# GPS.net
KiCad netlist of a schematic drawn in Altium Designer
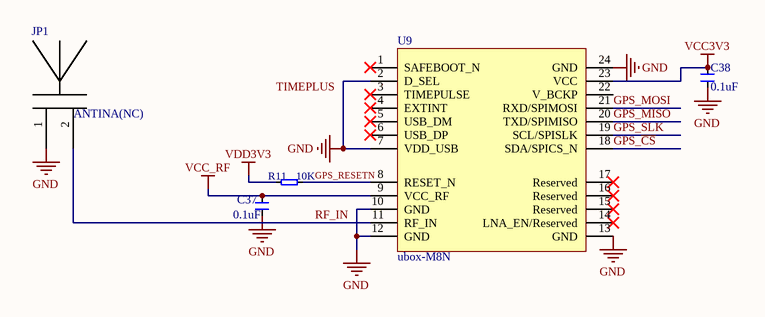
[diagram p0: GPS.SchDoc]

(export (version "E")
  (design (tool "Eeschema 10.0.6"))
  (components
    (comp (ref "C37") (value "0.1uF") (footprint "0603C") (libsource (lib "研发中心原理图库文件") (part "C")))
    (comp (ref "C38") (value "0.1uF") (footprint "0603C") (libsource (lib "研发中心原理图库文件") (part "C")))
    (comp (ref "JP1")
      (value "ANTINA(NC)")
      (footprint "研发中心PCB库文件:IPEX-20279-00E-03")
      (libsource (lib "研发中心原理图库文件") (part "ANTINA"))
    )
    (comp (ref "R11") (value "10K") (footprint "0603R") (libsource (lib "研发中心原理图库文件") (part "R")))
    (comp (ref "U9")
      (value "ubox-M8N")
      (footprint "研发中心PCB库文件:ublox-M8")
      (libsource (lib "研发中心原理图库文件") (part "ubox-M8N"))
    )
  )
  (nets
    (net (code "1") (name "/GPS_MISO") (class "Default")
      (node (ref "U9") (pin "20") (pinfunction "TXD/SPIMISO_20") (pintype "passive"))
    )
    (net (code "2") (name "/GPS_MOSI") (class "Default")
      (node (ref "U9") (pin "21") (pinfunction "RXD/SPIMOSI_21") (pintype "passive"))
    )
    (net (code "3") (name "/GPS_RESETN") (class "Default")
      (node (ref "R11") (pin "2") (pintype "passive"))
      (node (ref "U9") (pin "8") (pinfunction "RESET_N_8") (pintype "passive"))
    )
    (net (code "4") (name "/GPS_SLK") (class "Default")
      (node (ref "U9") (pin "19") (pinfunction "SCL/SPISLK_19") (pintype "passive"))
    )
    (net (code "5") (name "/GPS_~{CS}") (class "Default")
      (node (ref "U9") (pin "18") (pinfunction "SDA/SPICS_N_18") (pintype "passive"))
    )
    (net (code "6") (name "/RF_IN") (class "Default")
      (node (ref "JP1") (pin "2") (pinfunction "2_2") (pintype "passive"))
      (node (ref "U9") (pin "11") (pinfunction "RF_IN_11") (pintype "passive"))
    )
    (net (code "8") (name "GND") (class "Default")
      (node (ref "C37") (pin "2") (pintype "passive"))
      (node (ref "C38") (pin "1") (pintype "passive"))
      (node (ref "JP1") (pin "1") (pinfunction "1_1") (pintype "passive"))
      (node (ref "U9") (pin "10") (pinfunction "GND_10") (pintype "passive"))
      (node (ref "U9") (pin "12") (pinfunction "GND_12") (pintype "passive"))
      (node (ref "U9") (pin "13") (pinfunction "GND_13") (pintype "passive"))
      (node (ref "U9") (pin "2") (pinfunction "D_SEL_2") (pintype "passive"))
      (node (ref "U9") (pin "24") (pinfunction "GND_24") (pintype "passive"))
      (node (ref "U9") (pin "7") (pinfunction "VDD_USB_7") (pintype "passive"))
    )
    (net (code "9") (name "VCC3V3") (class "Default")
      (node (ref "C38") (pin "2") (pintype "passive"))
      (node (ref "U9") (pin "23") (pinfunction "VCC_23") (pintype "passive"))
    )
    (net (code "10") (name "VCC_RF") (class "Default")
      (node (ref "C37") (pin "1") (pintype "passive"))
      (node (ref "U9") (pin "9") (pinfunction "VCC_RF_9") (pintype "passive"))
    )
    (net (code "11") (name "VDD3V3") (class "Default") (node (ref "R11") (pin "1") (pintype "passive")))
    (net (code "12") (name "unconnected-(U9-EXTINT-Pad4)") (class "Default")
      (node (ref "U9") (pin "4") (pinfunction "EXTINT_4") (pintype "passive+no_connect"))
    )
    (net (code "13") (name "unconnected-(U9-LNA_EN{slash}Reserved-Pad14)") (class "Default")
      (node (ref "U9") (pin "14") (pinfunction "LNA_EN/Reserved_14") (pintype "passive+no_connect"))
    )
    (net (code "14") (name "unconnected-(U9-Reserved-Pad15)") (class "Default")
      (node (ref "U9") (pin "15") (pinfunction "Reserved_15") (pintype "passive+no_connect"))
    )
    (net (code "15") (name "unconnected-(U9-Reserved-Pad16)") (class "Default")
      (node (ref "U9") (pin "16") (pinfunction "Reserved_16") (pintype "passive+no_connect"))
    )
    (net (code "16") (name "unconnected-(U9-Reserved-Pad17)") (class "Default")
      (node (ref "U9") (pin "17") (pinfunction "Reserved_17") (pintype "passive+no_connect"))
    )
    (net (code "17") (name "unconnected-(U9-SAFEBOOT_N-Pad1)") (class "Default")
      (node (ref "U9") (pin "1") (pinfunction "SAFEBOOT_N_1") (pintype "passive+no_connect"))
    )
    (net (code "18") (name "unconnected-(U9-TIMEPULSE-Pad3)") (class "Default")
      (node (ref "U9") (pin "3") (pinfunction "TIMEPULSE_3") (pintype "passive+no_connect"))
    )
    (net (code "19") (name "unconnected-(U9-USB_DM-Pad5)") (class "Default")
      (node (ref "U9") (pin "5") (pinfunction "USB_DM_5") (pintype "passive+no_connect"))
    )
    (net (code "20") (name "unconnected-(U9-USB_DP-Pad6)") (class "Default")
      (node (ref "U9") (pin "6") (pinfunction "USB_DP_6") (pintype "passive+no_connect"))
    )
    (net (code "21") (name "unconnected-(U9-V_BCKP-Pad22)") (class "Default")
      (node (ref "U9") (pin "22") (pinfunction "V_BCKP_22") (pintype "passive"))
    )
  )
)
